# MDM_V3_PotPad_A.net
KiCad netlist of a schematic drawn in EAGLE
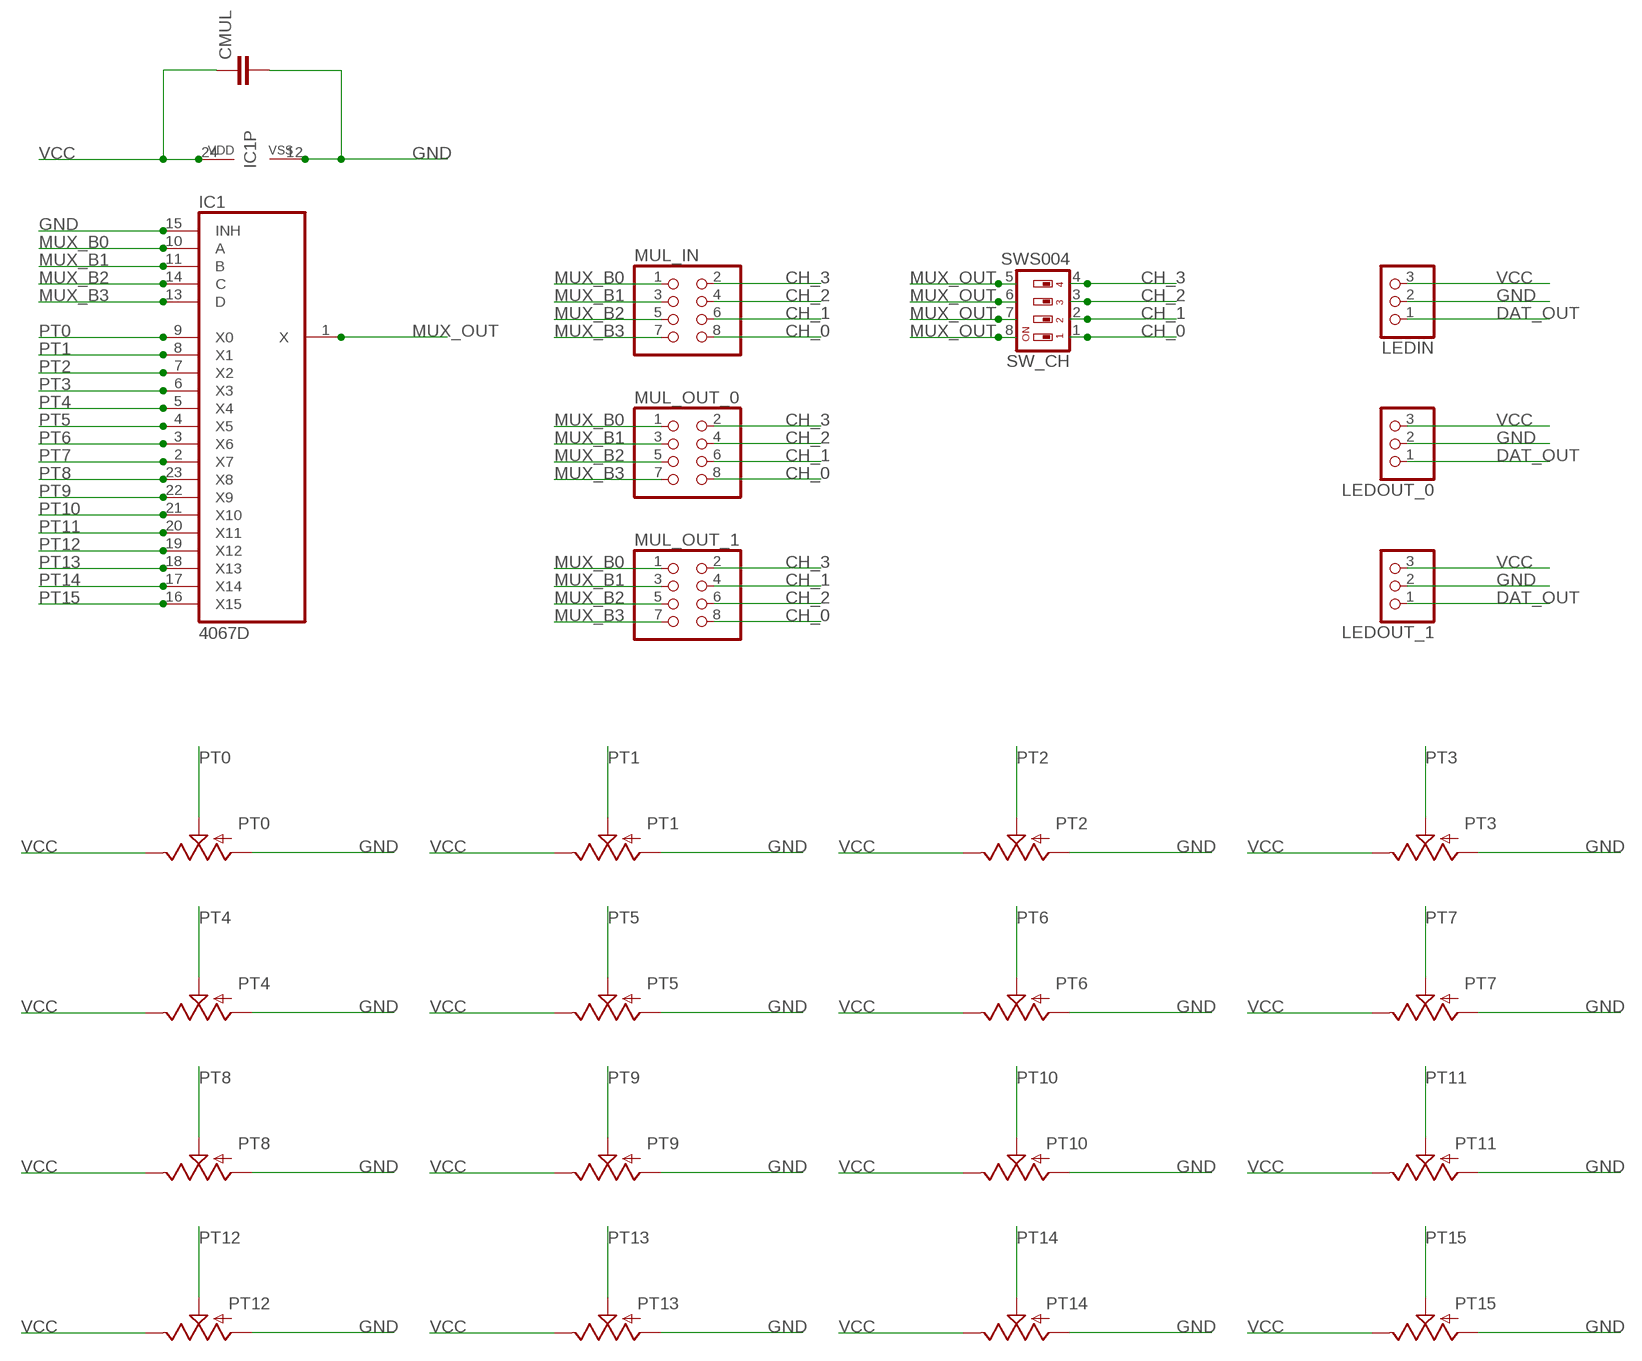
[diagram p0: schematic, sheet 1]

(export (version "E")
  (design (tool "Eeschema 10.0.6"))
  (components
    (comp (ref "CMUL")
      (value "C-EUC1206K")
      (footprint "eagle-import:C1206K")
      (libsource (lib "eagle-import") (part "C-EUC1206K"))
    )
    (comp (ref "IC1")
      (value "4067D")
      (footprint "eagle-import:SO24W")
      (libsource (lib "eagle-import") (part "4067D"))
    )
    (comp (ref "LEDIN")
      (value "PINHD-1X3")
      (footprint "eagle-import:1X03")
      (libsource (lib "eagle-import") (part "PINHD-1X3"))
    )
    (comp (ref "LEDOUT_0")
      (value "PINHD-1X3")
      (footprint "eagle-import:1X03")
      (libsource (lib "eagle-import") (part "PINHD-1X3"))
    )
    (comp (ref "LEDOUT_1")
      (value "PINHD-1X3")
      (footprint "eagle-import:1X03")
      (libsource (lib "eagle-import") (part "PINHD-1X3"))
    )
    (comp (ref "MUL_IN")
      (value "PINHD-2X4")
      (footprint "eagle-import:2X04")
      (libsource (lib "eagle-import") (part "PINHD-2X4"))
    )
    (comp (ref "MUL_OUT_0")
      (value "PINHD-2X4")
      (footprint "eagle-import:2X04")
      (libsource (lib "eagle-import") (part "PINHD-2X4"))
    )
    (comp (ref "MUL_OUT_1")
      (value "PINHD-2X4")
      (footprint "eagle-import:2X04")
      (libsource (lib "eagle-import") (part "PINHD-2X4"))
    )
    (comp (ref "PT0")
      (value "POT")
      (footprint "eagle-import:ALPS_POT")
      (libsource (lib "eagle-import") (part "POT"))
    )
    (comp (ref "PT1")
      (value "POT")
      (footprint "eagle-import:ALPS_POT")
      (libsource (lib "eagle-import") (part "POT"))
    )
    (comp (ref "PT2")
      (value "POT")
      (footprint "eagle-import:ALPS_POT")
      (libsource (lib "eagle-import") (part "POT"))
    )
    (comp (ref "PT3")
      (value "POT")
      (footprint "eagle-import:ALPS_POT")
      (libsource (lib "eagle-import") (part "POT"))
    )
    (comp (ref "PT4")
      (value "POT")
      (footprint "eagle-import:ALPS_POT")
      (libsource (lib "eagle-import") (part "POT"))
    )
    (comp (ref "PT5")
      (value "POT")
      (footprint "eagle-import:ALPS_POT")
      (libsource (lib "eagle-import") (part "POT"))
    )
    (comp (ref "PT6")
      (value "POT")
      (footprint "eagle-import:ALPS_POT")
      (libsource (lib "eagle-import") (part "POT"))
    )
    (comp (ref "PT7")
      (value "POT")
      (footprint "eagle-import:ALPS_POT")
      (libsource (lib "eagle-import") (part "POT"))
    )
    (comp (ref "PT8")
      (value "POT")
      (footprint "eagle-import:ALPS_POT")
      (libsource (lib "eagle-import") (part "POT"))
    )
    (comp (ref "PT9")
      (value "POT")
      (footprint "eagle-import:ALPS_POT")
      (libsource (lib "eagle-import") (part "POT"))
    )
    (comp (ref "PT10")
      (value "POT")
      (footprint "eagle-import:ALPS_POT")
      (libsource (lib "eagle-import") (part "POT"))
    )
    (comp (ref "PT11")
      (value "POT")
      (footprint "eagle-import:ALPS_POT")
      (libsource (lib "eagle-import") (part "POT"))
    )
    (comp (ref "PT12")
      (value "POT")
      (footprint "eagle-import:ALPS_POT")
      (libsource (lib "eagle-import") (part "POT"))
    )
    (comp (ref "PT13")
      (value "POT")
      (footprint "eagle-import:ALPS_POT")
      (libsource (lib "eagle-import") (part "POT"))
    )
    (comp (ref "PT14")
      (value "POT")
      (footprint "eagle-import:ALPS_POT")
      (libsource (lib "eagle-import") (part "POT"))
    )
    (comp (ref "PT15")
      (value "POT")
      (footprint "eagle-import:ALPS_POT")
      (libsource (lib "eagle-import") (part "POT"))
    )
    (comp (ref "SW_CH")
      (value "SWS004")
      (footprint "eagle-import:SMS-004")
      (libsource (lib "eagle-import") (part "SWS004"))
    )
  )
  (nets
    (net (code "1") (name "/CH_0") (class "Default")
      (node (ref "MUL_IN") (pin "8") (pinfunction "8_8") (pintype "passive"))
      (node (ref "MUL_OUT_0") (pin "8") (pinfunction "8_8") (pintype "passive"))
      (node (ref "MUL_OUT_1") (pin "8") (pinfunction "8_8") (pintype "passive"))
      (node (ref "SW_CH") (pin "1") (pinfunction "1_1") (pintype "passive"))
    )
    (net (code "2") (name "/CH_1") (class "Default")
      (node (ref "MUL_IN") (pin "6") (pinfunction "6_6") (pintype "passive"))
      (node (ref "MUL_OUT_0") (pin "6") (pinfunction "6_6") (pintype "passive"))
      (node (ref "MUL_OUT_1") (pin "4") (pinfunction "4_4") (pintype "passive"))
      (node (ref "SW_CH") (pin "2") (pinfunction "2_2") (pintype "passive"))
    )
    (net (code "3") (name "/CH_2") (class "Default")
      (node (ref "MUL_IN") (pin "4") (pinfunction "4_4") (pintype "passive"))
      (node (ref "MUL_OUT_0") (pin "4") (pinfunction "4_4") (pintype "passive"))
      (node (ref "MUL_OUT_1") (pin "6") (pinfunction "6_6") (pintype "passive"))
      (node (ref "SW_CH") (pin "3") (pinfunction "3_3") (pintype "passive"))
    )
    (net (code "4") (name "/CH_3") (class "Default")
      (node (ref "MUL_IN") (pin "2") (pinfunction "2_2") (pintype "passive"))
      (node (ref "MUL_OUT_0") (pin "2") (pinfunction "2_2") (pintype "passive"))
      (node (ref "MUL_OUT_1") (pin "2") (pinfunction "2_2") (pintype "passive"))
      (node (ref "SW_CH") (pin "4") (pinfunction "4_4") (pintype "passive"))
    )
    (net (code "5") (name "/DAT_OUT") (class "Default")
      (node (ref "LEDIN") (pin "1") (pinfunction "1_1") (pintype "passive"))
      (node (ref "LEDOUT_0") (pin "1") (pinfunction "1_1") (pintype "passive"))
      (node (ref "LEDOUT_1") (pin "1") (pinfunction "1_1") (pintype "passive"))
    )
    (net (code "6") (name "/GND") (class "Default")
      (node (ref "CMUL") (pin "2") (pinfunction "2_2") (pintype "passive"))
      (node (ref "IC1") (pin "12") (pinfunction "VSS_12") (pintype "power_in"))
      (node (ref "IC1") (pin "15") (pinfunction "INH_15") (pintype "input"))
      (node (ref "LEDIN") (pin "2") (pinfunction "2_2") (pintype "passive"))
      (node (ref "LEDOUT_0") (pin "2") (pinfunction "2_2") (pintype "passive"))
      (node (ref "LEDOUT_1") (pin "2") (pinfunction "2_2") (pintype "passive"))
      (node (ref "PT0") (pin "P$3") (pinfunction "A_P$3") (pintype "passive"))
      (node (ref "PT1") (pin "P$3") (pinfunction "A_P$3") (pintype "passive"))
      (node (ref "PT10") (pin "P$3") (pinfunction "A_P$3") (pintype "passive"))
      (node (ref "PT11") (pin "P$3") (pinfunction "A_P$3") (pintype "passive"))
      (node (ref "PT12") (pin "P$3") (pinfunction "A_P$3") (pintype "passive"))
      (node (ref "PT13") (pin "P$3") (pinfunction "A_P$3") (pintype "passive"))
      (node (ref "PT14") (pin "P$3") (pinfunction "A_P$3") (pintype "passive"))
      (node (ref "PT15") (pin "P$3") (pinfunction "A_P$3") (pintype "passive"))
      (node (ref "PT2") (pin "P$3") (pinfunction "A_P$3") (pintype "passive"))
      (node (ref "PT3") (pin "P$3") (pinfunction "A_P$3") (pintype "passive"))
      (node (ref "PT4") (pin "P$3") (pinfunction "A_P$3") (pintype "passive"))
      (node (ref "PT5") (pin "P$3") (pinfunction "A_P$3") (pintype "passive"))
      (node (ref "PT6") (pin "P$3") (pinfunction "A_P$3") (pintype "passive"))
      (node (ref "PT7") (pin "P$3") (pinfunction "A_P$3") (pintype "passive"))
      (node (ref "PT8") (pin "P$3") (pinfunction "A_P$3") (pintype "passive"))
      (node (ref "PT9") (pin "P$3") (pinfunction "A_P$3") (pintype "passive"))
    )
    (net (code "7") (name "/MUX_B0") (class "Default")
      (node (ref "IC1") (pin "10") (pinfunction "A_10") (pintype "input"))
      (node (ref "MUL_IN") (pin "1") (pinfunction "1_1") (pintype "passive"))
      (node (ref "MUL_OUT_0") (pin "1") (pinfunction "1_1") (pintype "passive"))
      (node (ref "MUL_OUT_1") (pin "1") (pinfunction "1_1") (pintype "passive"))
    )
    (net (code "8") (name "/MUX_B1") (class "Default")
      (node (ref "IC1") (pin "11") (pinfunction "B_11") (pintype "input"))
      (node (ref "MUL_IN") (pin "3") (pinfunction "3_3") (pintype "passive"))
      (node (ref "MUL_OUT_0") (pin "3") (pinfunction "3_3") (pintype "passive"))
      (node (ref "MUL_OUT_1") (pin "3") (pinfunction "3_3") (pintype "passive"))
    )
    (net (code "9") (name "/MUX_B2") (class "Default")
      (node (ref "IC1") (pin "14") (pinfunction "C_14") (pintype "input"))
      (node (ref "MUL_IN") (pin "5") (pinfunction "5_5") (pintype "passive"))
      (node (ref "MUL_OUT_0") (pin "5") (pinfunction "5_5") (pintype "passive"))
      (node (ref "MUL_OUT_1") (pin "5") (pinfunction "5_5") (pintype "passive"))
    )
    (net (code "10") (name "/MUX_B3") (class "Default")
      (node (ref "IC1") (pin "13") (pinfunction "D_13") (pintype "input"))
      (node (ref "MUL_IN") (pin "7") (pinfunction "7_7") (pintype "passive"))
      (node (ref "MUL_OUT_0") (pin "7") (pinfunction "7_7") (pintype "passive"))
      (node (ref "MUL_OUT_1") (pin "7") (pinfunction "7_7") (pintype "passive"))
    )
    (net (code "11") (name "/MUX_OUT") (class "Default")
      (node (ref "IC1") (pin "1") (pinfunction "X_1") (pintype "output"))
      (node (ref "SW_CH") (pin "5") (pinfunction "5_5") (pintype "passive"))
      (node (ref "SW_CH") (pin "6") (pinfunction "6_6") (pintype "passive"))
      (node (ref "SW_CH") (pin "7") (pinfunction "7_7") (pintype "passive"))
      (node (ref "SW_CH") (pin "8") (pinfunction "8_8") (pintype "passive"))
    )
    (net (code "12") (name "/PT0") (class "Default")
      (node (ref "IC1") (pin "9") (pinfunction "X0_9") (pintype "input"))
      (node (ref "PT0") (pin "P$2") (pinfunction "S_P$2") (pintype "passive"))
    )
    (net (code "13") (name "/PT1") (class "Default")
      (node (ref "IC1") (pin "8") (pinfunction "X1_8") (pintype "input"))
      (node (ref "PT1") (pin "P$2") (pinfunction "S_P$2") (pintype "passive"))
    )
    (net (code "14") (name "/PT2") (class "Default")
      (node (ref "IC1") (pin "7") (pinfunction "X2_7") (pintype "input"))
      (node (ref "PT2") (pin "P$2") (pinfunction "S_P$2") (pintype "passive"))
    )
    (net (code "15") (name "/PT3") (class "Default")
      (node (ref "IC1") (pin "6") (pinfunction "X3_6") (pintype "input"))
      (node (ref "PT3") (pin "P$2") (pinfunction "S_P$2") (pintype "passive"))
    )
    (net (code "16") (name "/PT4") (class "Default")
      (node (ref "IC1") (pin "5") (pinfunction "X4_5") (pintype "input"))
      (node (ref "PT4") (pin "P$2") (pinfunction "S_P$2") (pintype "passive"))
    )
    (net (code "17") (name "/PT5") (class "Default")
      (node (ref "IC1") (pin "4") (pinfunction "X5_4") (pintype "input"))
      (node (ref "PT5") (pin "P$2") (pinfunction "S_P$2") (pintype "passive"))
    )
    (net (code "18") (name "/PT6") (class "Default")
      (node (ref "IC1") (pin "3") (pinfunction "X6_3") (pintype "input"))
      (node (ref "PT6") (pin "P$2") (pinfunction "S_P$2") (pintype "passive"))
    )
    (net (code "19") (name "/PT7") (class "Default")
      (node (ref "IC1") (pin "2") (pinfunction "X7_2") (pintype "input"))
      (node (ref "PT7") (pin "P$2") (pinfunction "S_P$2") (pintype "passive"))
    )
    (net (code "20") (name "/PT8") (class "Default")
      (node (ref "IC1") (pin "23") (pinfunction "X8_23") (pintype "input"))
      (node (ref "PT8") (pin "P$2") (pinfunction "S_P$2") (pintype "passive"))
    )
    (net (code "21") (name "/PT9") (class "Default")
      (node (ref "IC1") (pin "22") (pinfunction "X9_22") (pintype "input"))
      (node (ref "PT9") (pin "P$2") (pinfunction "S_P$2") (pintype "passive"))
    )
    (net (code "22") (name "/PT10") (class "Default")
      (node (ref "IC1") (pin "21") (pinfunction "X10_21") (pintype "input"))
      (node (ref "PT10") (pin "P$2") (pinfunction "S_P$2") (pintype "passive"))
    )
    (net (code "23") (name "/PT11") (class "Default")
      (node (ref "IC1") (pin "20") (pinfunction "X11_20") (pintype "input"))
      (node (ref "PT11") (pin "P$2") (pinfunction "S_P$2") (pintype "passive"))
    )
    (net (code "24") (name "/PT12") (class "Default")
      (node (ref "IC1") (pin "19") (pinfunction "X12_19") (pintype "input"))
      (node (ref "PT12") (pin "P$2") (pinfunction "S_P$2") (pintype "passive"))
    )
    (net (code "25") (name "/PT13") (class "Default")
      (node (ref "IC1") (pin "18") (pinfunction "X13_18") (pintype "input"))
      (node (ref "PT13") (pin "P$2") (pinfunction "S_P$2") (pintype "passive"))
    )
    (net (code "26") (name "/PT14") (class "Default")
      (node (ref "IC1") (pin "17") (pinfunction "X14_17") (pintype "input"))
      (node (ref "PT14") (pin "P$2") (pinfunction "S_P$2") (pintype "passive"))
    )
    (net (code "27") (name "/PT15") (class "Default")
      (node (ref "IC1") (pin "16") (pinfunction "X15_16") (pintype "input"))
      (node (ref "PT15") (pin "P$2") (pinfunction "S_P$2") (pintype "passive"))
    )
    (net (code "28") (name "/VCC") (class "Default")
      (node (ref "CMUL") (pin "1") (pinfunction "1_1") (pintype "passive"))
      (node (ref "IC1") (pin "24") (pinfunction "VDD_24") (pintype "power_in"))
      (node (ref "LEDIN") (pin "3") (pinfunction "3_3") (pintype "passive"))
      (node (ref "LEDOUT_0") (pin "3") (pinfunction "3_3") (pintype "passive"))
      (node (ref "LEDOUT_1") (pin "3") (pinfunction "3_3") (pintype "passive"))
      (node (ref "PT0") (pin "P$1") (pinfunction "E_P$1") (pintype "passive"))
      (node (ref "PT1") (pin "P$1") (pinfunction "E_P$1") (pintype "passive"))
      (node (ref "PT10") (pin "P$1") (pinfunction "E_P$1") (pintype "passive"))
      (node (ref "PT11") (pin "P$1") (pinfunction "E_P$1") (pintype "passive"))
      (node (ref "PT12") (pin "P$1") (pinfunction "E_P$1") (pintype "passive"))
      (node (ref "PT13") (pin "P$1") (pinfunction "E_P$1") (pintype "passive"))
      (node (ref "PT14") (pin "P$1") (pinfunction "E_P$1") (pintype "passive"))
      (node (ref "PT15") (pin "P$1") (pinfunction "E_P$1") (pintype "passive"))
      (node (ref "PT2") (pin "P$1") (pinfunction "E_P$1") (pintype "passive"))
      (node (ref "PT3") (pin "P$1") (pinfunction "E_P$1") (pintype "passive"))
      (node (ref "PT4") (pin "P$1") (pinfunction "E_P$1") (pintype "passive"))
      (node (ref "PT5") (pin "P$1") (pinfunction "E_P$1") (pintype "passive"))
      (node (ref "PT6") (pin "P$1") (pinfunction "E_P$1") (pintype "passive"))
      (node (ref "PT7") (pin "P$1") (pinfunction "E_P$1") (pintype "passive"))
      (node (ref "PT8") (pin "P$1") (pinfunction "E_P$1") (pintype "passive"))
      (node (ref "PT9") (pin "P$1") (pinfunction "E_P$1") (pintype "passive"))
    )
  )
)
